# Nixie_Uhr.net
KiCad netlist of a schematic drawn in EAGLE
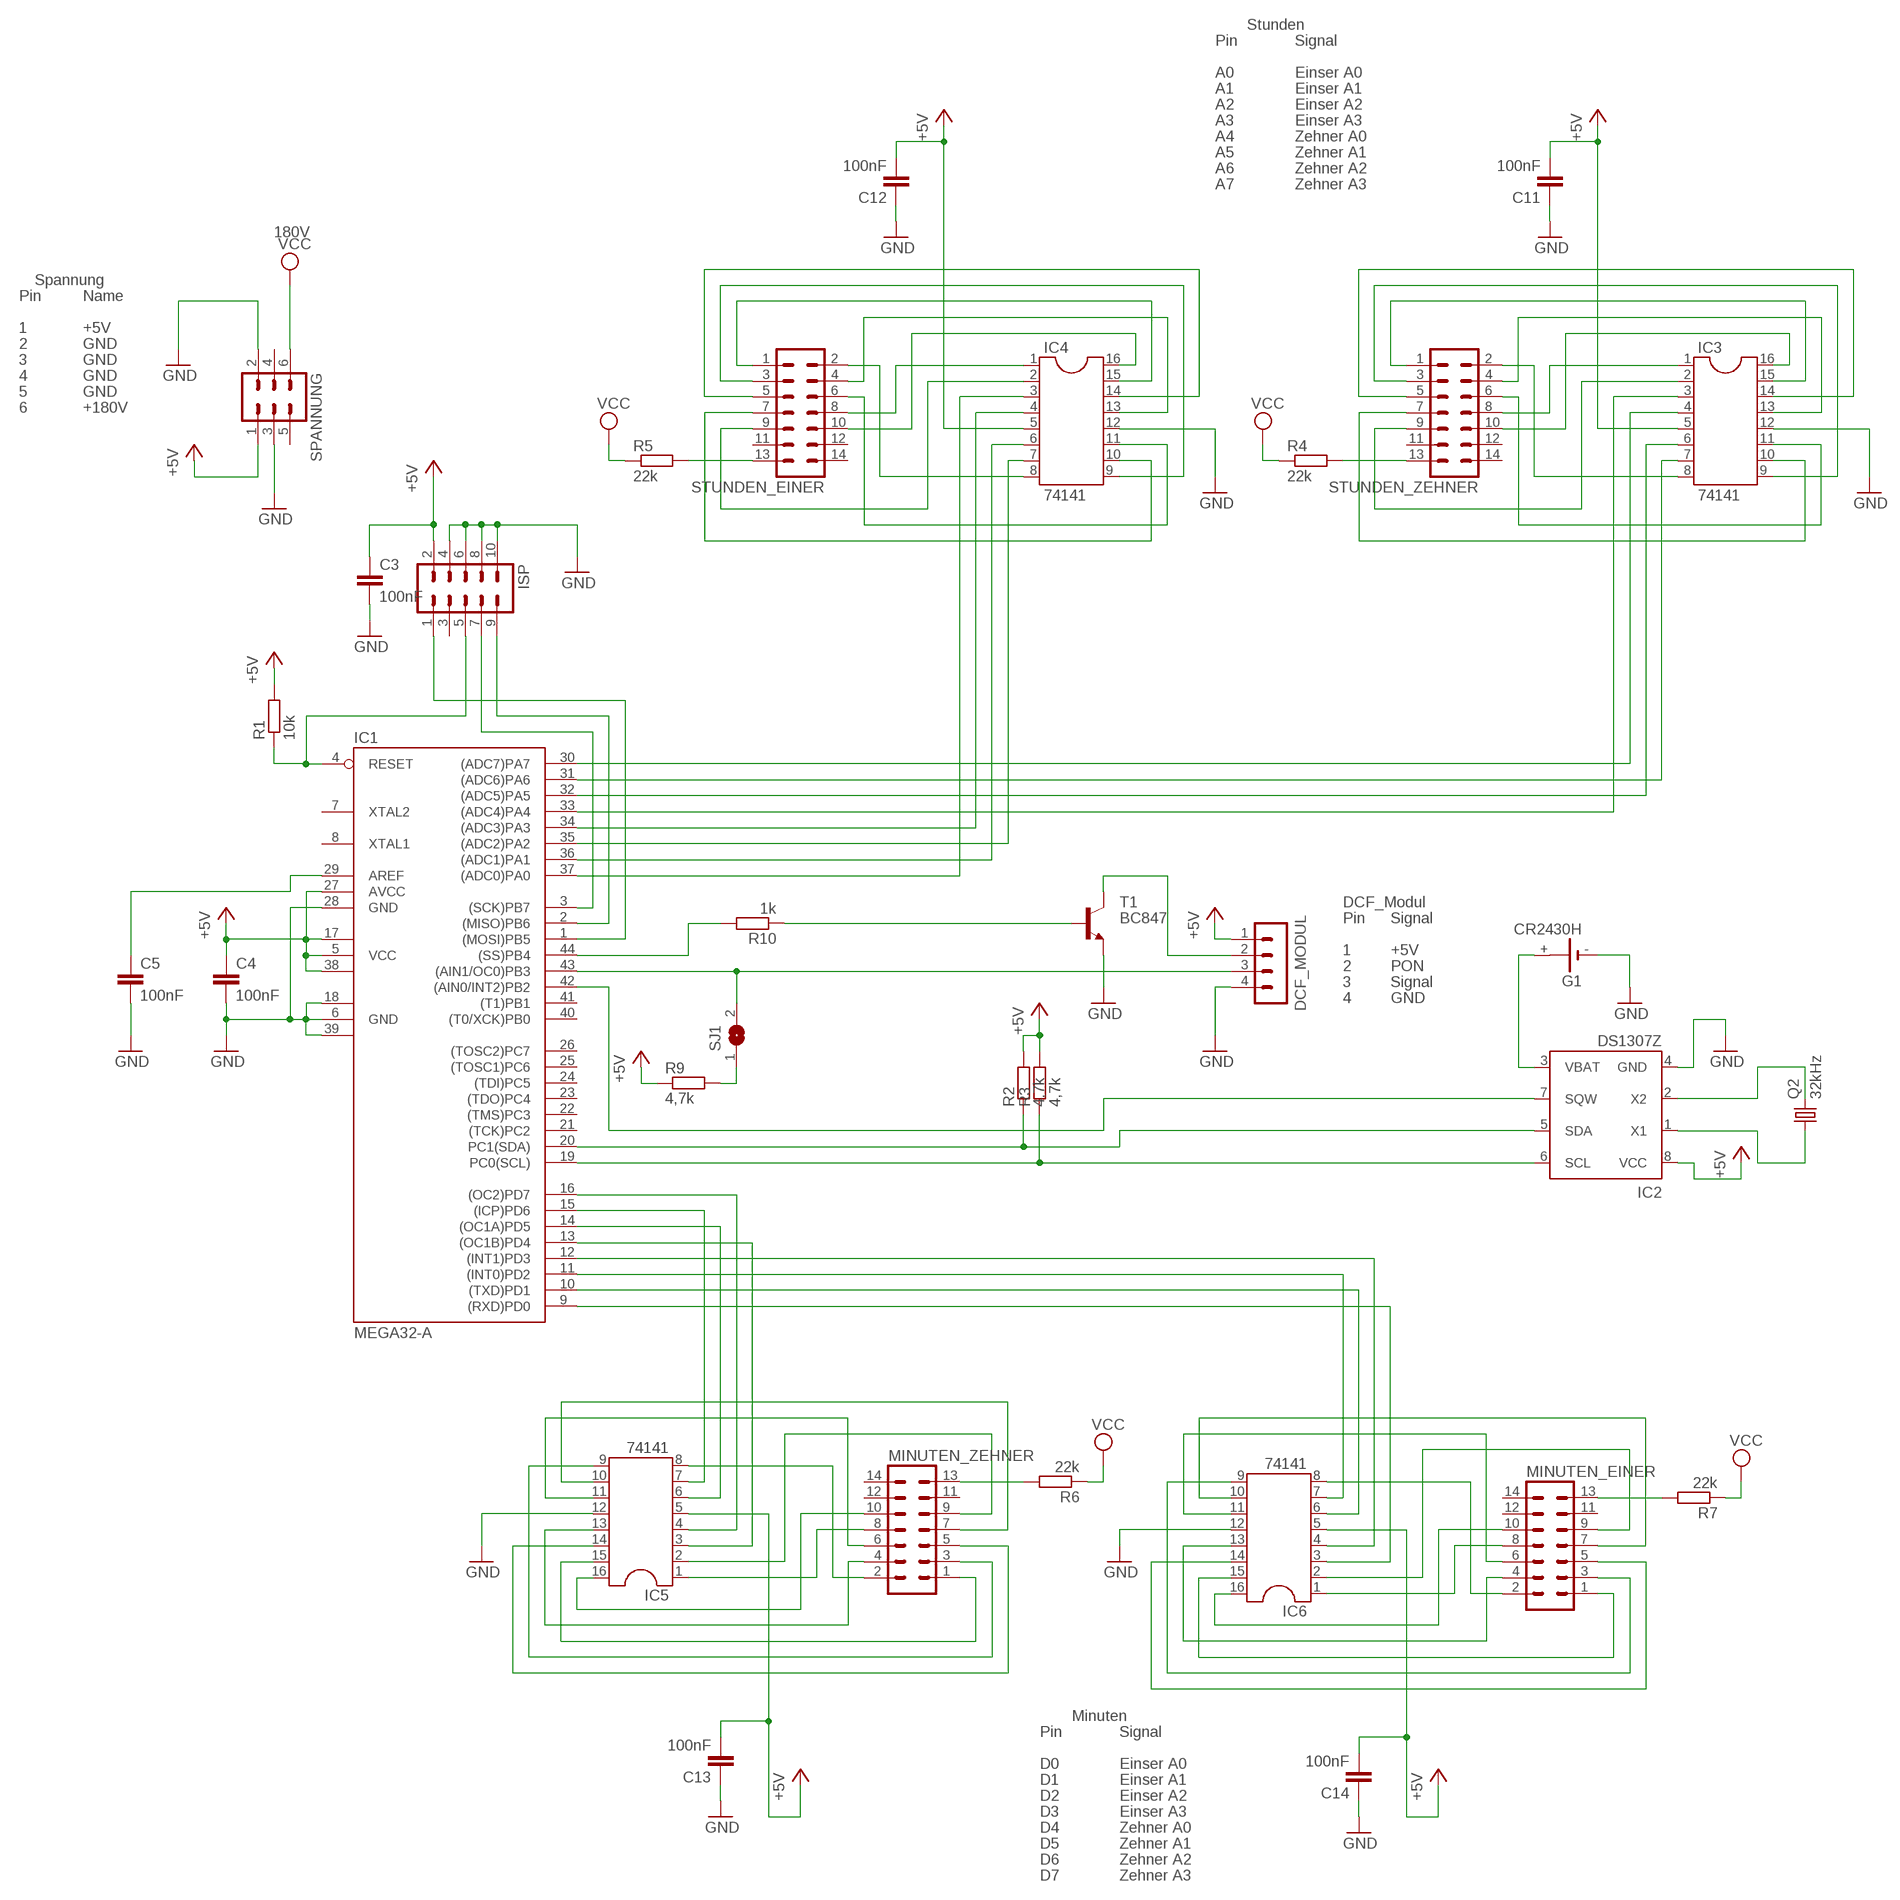
[diagram p0: schematic, sheet 1]

(export (version "E")
  (design (tool "Eeschema 10.0.6"))
  (components
    (comp (ref "C3")
      (value "100nF")
      (footprint "eagle-import:C0805")
      (libsource (lib "eagle-import") (part "C-EUC0805"))
    )
    (comp (ref "C4")
      (value "100nF")
      (footprint "eagle-import:C0805")
      (libsource (lib "eagle-import") (part "C-EUC0805"))
    )
    (comp (ref "C5")
      (value "100nF")
      (footprint "eagle-import:C0805")
      (libsource (lib "eagle-import") (part "C-EUC0805"))
    )
    (comp (ref "C11")
      (value "100nF")
      (footprint "eagle-import:C0805")
      (libsource (lib "eagle-import") (part "C-EUC0805"))
    )
    (comp (ref "C12")
      (value "100nF")
      (footprint "eagle-import:C0805")
      (libsource (lib "eagle-import") (part "C-EUC0805"))
    )
    (comp (ref "C13")
      (value "100nF")
      (footprint "eagle-import:C0805")
      (libsource (lib "eagle-import") (part "C-EUC0805"))
    )
    (comp (ref "C14")
      (value "100nF")
      (footprint "eagle-import:C0805")
      (libsource (lib "eagle-import") (part "C-EUC0805"))
    )
    (comp (ref "DCF_MODUL")
      (value "MA04-1")
      (footprint "eagle-import:MA04-1")
      (libsource (lib "eagle-import") (part "MA04-1"))
    )
    (comp (ref "G1")
      (value "CR2430H")
      (footprint "eagle-import:CR2430H")
      (libsource (lib "eagle-import") (part "CR2430H"))
    )
    (comp (ref "IC1")
      (value "MEGA32-A")
      (footprint "eagle-import:TQFP44")
      (fields (field (name "MPN") "ATMEGA32-16AU"))
      (libsource (lib "eagle-import") (part "MEGA32-A"))
    )
    (comp (ref "IC2")
      (value "DS1307Z")
      (footprint "eagle-import:SOIC8")
      (libsource (lib "eagle-import") (part "DS1307Z"))
    )
    (comp (ref "IC3")
      (value "74141")
      (footprint "eagle-import:DIL16")
      (libsource (lib "eagle-import") (part "DIL16"))
    )
    (comp (ref "IC4")
      (value "74141")
      (footprint "eagle-import:DIL16")
      (libsource (lib "eagle-import") (part "DIL16"))
    )
    (comp (ref "IC5")
      (value "74141")
      (footprint "eagle-import:DIL16")
      (libsource (lib "eagle-import") (part "DIL16"))
    )
    (comp (ref "IC6")
      (value "74141")
      (footprint "eagle-import:DIL16")
      (libsource (lib "eagle-import") (part "DIL16"))
    )
    (comp (ref "ISP")
      (value "ML10")
      (footprint "eagle-import:ML10")
      (libsource (lib "eagle-import") (part "ML10"))
    )
    (comp (ref "MINUTEN_EINER")
      (value "ML14")
      (footprint "eagle-import:ML14")
      (libsource (lib "eagle-import") (part "ML14"))
    )
    (comp (ref "MINUTEN_ZEHNER")
      (value "ML14")
      (footprint "eagle-import:ML14")
      (libsource (lib "eagle-import") (part "ML14"))
    )
    (comp (ref "Q2")
      (value "32kHz")
      (footprint "eagle-import:TC26V")
      (libsource (lib "eagle-import") (part "CRYSTALTC26V"))
    )
    (comp (ref "R1")
      (value "10k")
      (footprint "eagle-import:R0805")
      (libsource (lib "eagle-import") (part "R-EU_R0805"))
    )
    (comp (ref "R2")
      (value "4,7k")
      (footprint "eagle-import:R0805")
      (libsource (lib "eagle-import") (part "R-EU_R0805"))
    )
    (comp (ref "R3")
      (value "4,7k")
      (footprint "eagle-import:R0805")
      (libsource (lib "eagle-import") (part "R-EU_R0805"))
    )
    (comp (ref "R4")
      (value "22k")
      (footprint "eagle-import:0204_7")
      (libsource (lib "eagle-import") (part "R-EU_0204/7"))
    )
    (comp (ref "R5")
      (value "22k")
      (footprint "eagle-import:0204_7")
      (libsource (lib "eagle-import") (part "R-EU_0204/7"))
    )
    (comp (ref "R6")
      (value "22k")
      (footprint "eagle-import:0204_7")
      (libsource (lib "eagle-import") (part "R-EU_0204/7"))
    )
    (comp (ref "R7")
      (value "22k")
      (footprint "eagle-import:0204_7")
      (libsource (lib "eagle-import") (part "R-EU_0204/7"))
    )
    (comp (ref "R9")
      (value "4,7k")
      (footprint "eagle-import:R0805")
      (libsource (lib "eagle-import") (part "R-EU_R0805"))
    )
    (comp (ref "R10")
      (value "1k")
      (footprint "eagle-import:R0805")
      (libsource (lib "eagle-import") (part "R-EU_R0805"))
    )
    (comp (ref "SJ1") (value "SJ") (footprint "eagle-import:SJ") (libsource (lib "eagle-import") (part "SJ")))
    (comp (ref "SPANNUNG")
      (value "ML6")
      (footprint "eagle-import:ML6")
      (libsource (lib "eagle-import") (part "ML6"))
    )
    (comp (ref "STUNDEN_EINER")
      (value "ML14")
      (footprint "eagle-import:ML14")
      (libsource (lib "eagle-import") (part "ML14"))
    )
    (comp (ref "STUNDEN_ZEHNER")
      (value "ML14")
      (footprint "eagle-import:ML14")
      (libsource (lib "eagle-import") (part "ML14"))
    )
    (comp (ref "T1")
      (value "BC847")
      (footprint "eagle-import:SOT23")
      (libsource (lib "eagle-import") (part "BC847"))
    )
  )
  (nets
    (net (code "1") (name "+5V") (class "Default")
      (node (ref "C11") (pin "2") (pinfunction "2_2") (pintype "passive"))
      (node (ref "C12") (pin "2") (pinfunction "2_2") (pintype "passive"))
      (node (ref "C13") (pin "2") (pinfunction "2_2") (pintype "passive"))
      (node (ref "C14") (pin "2") (pinfunction "2_2") (pintype "passive"))
      (node (ref "C3") (pin "1") (pinfunction "1_1") (pintype "passive"))
      (node (ref "C4") (pin "1") (pinfunction "1_1") (pintype "passive"))
      (node (ref "DCF_MODUL") (pin "1") (pinfunction "1_1") (pintype "passive"))
      (node (ref "IC1") (pin "17") (pinfunction "VCC1_17") (pintype "power_in"))
      (node (ref "IC1") (pin "27") (pinfunction "AVCC_27") (pintype "power_in"))
      (node (ref "IC1") (pin "38") (pinfunction "VCC2_38") (pintype "power_in"))
      (node (ref "IC1") (pin "5") (pinfunction "VCC_5") (pintype "power_in"))
      (node (ref "IC2") (pin "8") (pinfunction "VCC_8") (pintype "power_in"))
      (node (ref "IC3") (pin "5") (pinfunction "5_5") (pintype "passive"))
      (node (ref "IC4") (pin "5") (pinfunction "5_5") (pintype "passive"))
      (node (ref "IC5") (pin "5") (pinfunction "5_5") (pintype "passive"))
      (node (ref "IC6") (pin "5") (pinfunction "5_5") (pintype "passive"))
      (node (ref "ISP") (pin "2") (pinfunction "2_2") (pintype "passive"))
      (node (ref "R1") (pin "2") (pinfunction "2_2") (pintype "passive"))
      (node (ref "R2") (pin "2") (pinfunction "2_2") (pintype "passive"))
      (node (ref "R3") (pin "2") (pinfunction "2_2") (pintype "passive"))
      (node (ref "R9") (pin "1") (pinfunction "1_1") (pintype "passive"))
      (node (ref "SPANNUNG") (pin "1") (pinfunction "1_1") (pintype "passive"))
    )
    (net (code "2") (name "GND") (class "Default")
      (node (ref "C11") (pin "1") (pinfunction "1_1") (pintype "passive"))
      (node (ref "C12") (pin "1") (pinfunction "1_1") (pintype "passive"))
      (node (ref "C13") (pin "1") (pinfunction "1_1") (pintype "passive"))
      (node (ref "C14") (pin "1") (pinfunction "1_1") (pintype "passive"))
      (node (ref "C3") (pin "2") (pinfunction "2_2") (pintype "passive"))
      (node (ref "C4") (pin "2") (pinfunction "2_2") (pintype "passive"))
      (node (ref "C5") (pin "2") (pinfunction "2_2") (pintype "passive"))
      (node (ref "DCF_MODUL") (pin "4") (pinfunction "4_4") (pintype "passive"))
      (node (ref "G1") (pin "-") (pinfunction "-_-") (pintype "passive"))
      (node (ref "IC1") (pin "18") (pinfunction "GND1_18") (pintype "power_in"))
      (node (ref "IC1") (pin "28") (pinfunction "GND_28") (pintype "power_in"))
      (node (ref "IC1") (pin "39") (pinfunction "GND2_39") (pintype "power_in"))
      (node (ref "IC1") (pin "6") (pinfunction "GND_6") (pintype "power_in"))
      (node (ref "IC2") (pin "4") (pinfunction "GND_4") (pintype "power_in"))
      (node (ref "IC3") (pin "12") (pinfunction "12_12") (pintype "passive"))
      (node (ref "IC4") (pin "12") (pinfunction "12_12") (pintype "passive"))
      (node (ref "IC5") (pin "12") (pinfunction "12_12") (pintype "passive"))
      (node (ref "IC6") (pin "12") (pinfunction "12_12") (pintype "passive"))
      (node (ref "ISP") (pin "10") (pinfunction "10_10") (pintype "passive"))
      (node (ref "ISP") (pin "4") (pinfunction "4_4") (pintype "passive"))
      (node (ref "ISP") (pin "6") (pinfunction "6_6") (pintype "passive"))
      (node (ref "ISP") (pin "8") (pinfunction "8_8") (pintype "passive"))
      (node (ref "SPANNUNG") (pin "2") (pinfunction "2_2") (pintype "passive"))
      (node (ref "SPANNUNG") (pin "3") (pinfunction "3_3") (pintype "passive"))
      (node (ref "T1") (pin "2") (pinfunction "E_2") (pintype "passive"))
    )
    (net (code "3") (name "Net-(IC1-(ADC0)PA0)") (class "Default")
      (node (ref "IC1") (pin "37") (pinfunction "(ADC0)PA0_37") (pintype "bidirectional"))
      (node (ref "IC4") (pin "3") (pinfunction "3_3") (pintype "passive"))
    )
    (net (code "4") (name "Net-(IC1-(ADC1)PA1)") (class "Default")
      (node (ref "IC1") (pin "36") (pinfunction "(ADC1)PA1_36") (pintype "bidirectional"))
      (node (ref "IC4") (pin "6") (pinfunction "6_6") (pintype "passive"))
    )
    (net (code "5") (name "Net-(IC1-(ADC2)PA2)") (class "Default")
      (node (ref "IC1") (pin "35") (pinfunction "(ADC2)PA2_35") (pintype "bidirectional"))
      (node (ref "IC4") (pin "7") (pinfunction "7_7") (pintype "passive"))
    )
    (net (code "6") (name "Net-(IC1-(ADC3)PA3)") (class "Default")
      (node (ref "IC1") (pin "34") (pinfunction "(ADC3)PA3_34") (pintype "bidirectional"))
      (node (ref "IC4") (pin "4") (pinfunction "4_4") (pintype "passive"))
    )
    (net (code "7") (name "Net-(IC1-(ADC4)PA4)") (class "Default")
      (node (ref "IC1") (pin "33") (pinfunction "(ADC4)PA4_33") (pintype "bidirectional"))
      (node (ref "IC3") (pin "3") (pinfunction "3_3") (pintype "passive"))
    )
    (net (code "8") (name "Net-(IC1-(ADC5)PA5)") (class "Default")
      (node (ref "IC1") (pin "32") (pinfunction "(ADC5)PA5_32") (pintype "bidirectional"))
      (node (ref "IC3") (pin "6") (pinfunction "6_6") (pintype "passive"))
    )
    (net (code "9") (name "Net-(IC1-(ADC6)PA6)") (class "Default")
      (node (ref "IC1") (pin "31") (pinfunction "(ADC6)PA6_31") (pintype "bidirectional"))
      (node (ref "IC3") (pin "7") (pinfunction "7_7") (pintype "passive"))
    )
    (net (code "10") (name "Net-(IC1-(ADC7)PA7)") (class "Default")
      (node (ref "IC1") (pin "30") (pinfunction "(ADC7)PA7_30") (pintype "bidirectional"))
      (node (ref "IC3") (pin "4") (pinfunction "4_4") (pintype "passive"))
    )
    (net (code "11") (name "Net-(IC1-(AIN0{slash}INT2)PB2)") (class "Default")
      (node (ref "IC1") (pin "42") (pinfunction "(AIN0/INT2)PB2_42") (pintype "bidirectional"))
      (node (ref "IC2") (pin "7") (pinfunction "SQW_7") (pintype "open_collector"))
    )
    (net (code "12") (name "Net-(IC1-(AIN1{slash}OC0)PB3)") (class "Default")
      (node (ref "DCF_MODUL") (pin "3") (pinfunction "3_3") (pintype "passive"))
      (node (ref "IC1") (pin "43") (pinfunction "(AIN1/OC0)PB3_43") (pintype "bidirectional"))
      (node (ref "SJ1") (pin "2") (pinfunction "2_2") (pintype "passive"))
    )
    (net (code "13") (name "Net-(IC1-(ICP)PD6)") (class "Default")
      (node (ref "IC1") (pin "15") (pinfunction "(ICP)PD6_15") (pintype "bidirectional"))
      (node (ref "IC5") (pin "7") (pinfunction "7_7") (pintype "passive"))
    )
    (net (code "14") (name "Net-(IC1-(INT0)PD2)") (class "Default")
      (node (ref "IC1") (pin "11") (pinfunction "(INT0)PD2_11") (pintype "bidirectional"))
      (node (ref "IC6") (pin "7") (pinfunction "7_7") (pintype "passive"))
    )
    (net (code "15") (name "Net-(IC1-(INT1)PD3)") (class "Default")
      (node (ref "IC1") (pin "12") (pinfunction "(INT1)PD3_12") (pintype "bidirectional"))
      (node (ref "IC6") (pin "4") (pinfunction "4_4") (pintype "passive"))
    )
    (net (code "16") (name "Net-(IC1-(MISO)PB6)") (class "Default")
      (node (ref "IC1") (pin "2") (pinfunction "(MISO)PB6_2") (pintype "bidirectional"))
      (node (ref "ISP") (pin "9") (pinfunction "9_9") (pintype "passive"))
    )
    (net (code "17") (name "Net-(IC1-(MOSI)PB5)") (class "Default")
      (node (ref "IC1") (pin "1") (pinfunction "(MOSI)PB5_1") (pintype "bidirectional"))
      (node (ref "ISP") (pin "1") (pinfunction "1_1") (pintype "passive"))
    )
    (net (code "18") (name "Net-(IC1-(OC1A)PD5)") (class "Default")
      (node (ref "IC1") (pin "14") (pinfunction "(OC1A)PD5_14") (pintype "bidirectional"))
      (node (ref "IC5") (pin "6") (pinfunction "6_6") (pintype "passive"))
    )
    (net (code "19") (name "Net-(IC1-(OC1B)PD4)") (class "Default")
      (node (ref "IC1") (pin "13") (pinfunction "(OC1B)PD4_13") (pintype "bidirectional"))
      (node (ref "IC5") (pin "3") (pinfunction "3_3") (pintype "passive"))
    )
    (net (code "20") (name "Net-(IC1-(OC2)PD7)") (class "Default")
      (node (ref "IC1") (pin "16") (pinfunction "(OC2)PD7_16") (pintype "bidirectional"))
      (node (ref "IC5") (pin "4") (pinfunction "4_4") (pintype "passive"))
    )
    (net (code "21") (name "Net-(IC1-(RXD)PD0)") (class "Default")
      (node (ref "IC1") (pin "9") (pinfunction "(RXD)PD0_9") (pintype "bidirectional"))
      (node (ref "IC6") (pin "3") (pinfunction "3_3") (pintype "passive"))
    )
    (net (code "22") (name "Net-(IC1-(SCK)PB7)") (class "Default")
      (node (ref "IC1") (pin "3") (pinfunction "(SCK)PB7_3") (pintype "bidirectional"))
      (node (ref "ISP") (pin "7") (pinfunction "7_7") (pintype "passive"))
    )
    (net (code "23") (name "Net-(IC1-(SS)PB4)") (class "Default")
      (node (ref "IC1") (pin "44") (pinfunction "(SS)PB4_44") (pintype "bidirectional"))
      (node (ref "R10") (pin "2") (pinfunction "2_2") (pintype "passive"))
    )
    (net (code "24") (name "Net-(IC1-(TXD)PD1)") (class "Default")
      (node (ref "IC1") (pin "10") (pinfunction "(TXD)PD1_10") (pintype "bidirectional"))
      (node (ref "IC6") (pin "6") (pinfunction "6_6") (pintype "passive"))
    )
    (net (code "25") (name "Net-(IC1-AREF)") (class "Default")
      (node (ref "C5") (pin "1") (pinfunction "1_1") (pintype "passive"))
      (node (ref "IC1") (pin "29") (pinfunction "AREF_29") (pintype "passive"))
    )
    (net (code "26") (name "Net-(IC1-PC0(SCL))") (class "Default")
      (node (ref "IC1") (pin "19") (pinfunction "PC0(SCL)_19") (pintype "bidirectional"))
      (node (ref "IC2") (pin "6") (pinfunction "SCL_6") (pintype "input"))
      (node (ref "R3") (pin "1") (pinfunction "1_1") (pintype "passive"))
    )
    (net (code "27") (name "Net-(IC1-PC1(SDA))") (class "Default")
      (node (ref "IC1") (pin "20") (pinfunction "PC1(SDA)_20") (pintype "bidirectional"))
      (node (ref "IC2") (pin "5") (pinfunction "SDA_5") (pintype "bidirectional"))
      (node (ref "R2") (pin "1") (pinfunction "1_1") (pintype "passive"))
    )
    (net (code "28") (name "Net-(IC1-RESET)") (class "Default")
      (node (ref "IC1") (pin "4") (pinfunction "RESET_4") (pintype "input"))
      (node (ref "ISP") (pin "5") (pinfunction "5_5") (pintype "passive"))
      (node (ref "R1") (pin "1") (pinfunction "1_1") (pintype "passive"))
    )
    (net (code "29") (name "Net-(IC2-VBAT)") (class "Default")
      (node (ref "G1") (pin "+") (pinfunction "+_+") (pintype "passive"))
      (node (ref "IC2") (pin "3") (pinfunction "VBAT_3") (pintype "passive"))
    )
    (net (code "30") (name "Net-(IC2-X1)") (class "Default")
      (node (ref "IC2") (pin "1") (pinfunction "X1_1") (pintype "input"))
      (node (ref "Q2") (pin "1") (pinfunction "1_1") (pintype "passive"))
    )
    (net (code "31") (name "Net-(IC2-X2)") (class "Default")
      (node (ref "IC2") (pin "2") (pinfunction "X2_2") (pintype "output"))
      (node (ref "Q2") (pin "2") (pinfunction "2_2") (pintype "passive"))
    )
    (net (code "32") (name "Net-(IC3-Pad1)") (class "Default")
      (node (ref "IC3") (pin "1") (pinfunction "1_1") (pintype "passive"))
      (node (ref "STUNDEN_ZEHNER") (pin "8") (pinfunction "8_8") (pintype "passive"))
    )
    (net (code "33") (name "Net-(IC3-Pad2)") (class "Default")
      (node (ref "IC3") (pin "2") (pinfunction "2_2") (pintype "passive"))
      (node (ref "STUNDEN_ZEHNER") (pin "9") (pinfunction "9_9") (pintype "passive"))
    )
    (net (code "34") (name "Net-(IC3-Pad8)") (class "Default")
      (node (ref "IC3") (pin "8") (pinfunction "8_8") (pintype "passive"))
      (node (ref "STUNDEN_ZEHNER") (pin "2") (pinfunction "2_2") (pintype "passive"))
    )
    (net (code "35") (name "Net-(IC3-Pad9)") (class "Default")
      (node (ref "IC3") (pin "9") (pinfunction "9_9") (pintype "passive"))
      (node (ref "STUNDEN_ZEHNER") (pin "3") (pinfunction "3_3") (pintype "passive"))
    )
    (net (code "36") (name "Net-(IC3-Pad10)") (class "Default")
      (node (ref "IC3") (pin "10") (pinfunction "10_10") (pintype "passive"))
      (node (ref "STUNDEN_ZEHNER") (pin "7") (pinfunction "7_7") (pintype "passive"))
    )
    (net (code "37") (name "Net-(IC3-Pad11)") (class "Default")
      (node (ref "IC3") (pin "11") (pinfunction "11_11") (pintype "passive"))
      (node (ref "STUNDEN_ZEHNER") (pin "6") (pinfunction "6_6") (pintype "passive"))
    )
    (net (code "38") (name "Net-(IC3-Pad13)") (class "Default")
      (node (ref "IC3") (pin "13") (pinfunction "13_13") (pintype "passive"))
      (node (ref "STUNDEN_ZEHNER") (pin "4") (pinfunction "4_4") (pintype "passive"))
    )
    (net (code "39") (name "Net-(IC3-Pad14)") (class "Default")
      (node (ref "IC3") (pin "14") (pinfunction "14_14") (pintype "passive"))
      (node (ref "STUNDEN_ZEHNER") (pin "5") (pinfunction "5_5") (pintype "passive"))
    )
    (net (code "40") (name "Net-(IC3-Pad15)") (class "Default")
      (node (ref "IC3") (pin "15") (pinfunction "15_15") (pintype "passive"))
      (node (ref "STUNDEN_ZEHNER") (pin "1") (pinfunction "1_1") (pintype "passive"))
    )
    (net (code "41") (name "Net-(IC3-Pad16)") (class "Default")
      (node (ref "IC3") (pin "16") (pinfunction "16_16") (pintype "passive"))
      (node (ref "STUNDEN_ZEHNER") (pin "10") (pinfunction "10_10") (pintype "passive"))
    )
    (net (code "42") (name "Net-(IC4-Pad1)") (class "Default")
      (node (ref "IC4") (pin "1") (pinfunction "1_1") (pintype "passive"))
      (node (ref "STUNDEN_EINER") (pin "8") (pinfunction "8_8") (pintype "passive"))
    )
    (net (code "43") (name "Net-(IC4-Pad2)") (class "Default")
      (node (ref "IC4") (pin "2") (pinfunction "2_2") (pintype "passive"))
      (node (ref "STUNDEN_EINER") (pin "9") (pinfunction "9_9") (pintype "passive"))
    )
    (net (code "44") (name "Net-(IC4-Pad8)") (class "Default")
      (node (ref "IC4") (pin "8") (pinfunction "8_8") (pintype "passive"))
      (node (ref "STUNDEN_EINER") (pin "2") (pinfunction "2_2") (pintype "passive"))
    )
    (net (code "45") (name "Net-(IC4-Pad9)") (class "Default")
      (node (ref "IC4") (pin "9") (pinfunction "9_9") (pintype "passive"))
      (node (ref "STUNDEN_EINER") (pin "3") (pinfunction "3_3") (pintype "passive"))
    )
    (net (code "46") (name "Net-(IC4-Pad10)") (class "Default")
      (node (ref "IC4") (pin "10") (pinfunction "10_10") (pintype "passive"))
      (node (ref "STUNDEN_EINER") (pin "7") (pinfunction "7_7") (pintype "passive"))
    )
    (net (code "47") (name "Net-(IC4-Pad11)") (class "Default")
      (node (ref "IC4") (pin "11") (pinfunction "11_11") (pintype "passive"))
      (node (ref "STUNDEN_EINER") (pin "6") (pinfunction "6_6") (pintype "passive"))
    )
    (net (code "48") (name "Net-(IC4-Pad13)") (class "Default")
      (node (ref "IC4") (pin "13") (pinfunction "13_13") (pintype "passive"))
      (node (ref "STUNDEN_EINER") (pin "4") (pinfunction "4_4") (pintype "passive"))
    )
    (net (code "49") (name "Net-(IC4-Pad14)") (class "Default")
      (node (ref "IC4") (pin "14") (pinfunction "14_14") (pintype "passive"))
      (node (ref "STUNDEN_EINER") (pin "5") (pinfunction "5_5") (pintype "passive"))
    )
    (net (code "50") (name "Net-(IC4-Pad15)") (class "Default")
      (node (ref "IC4") (pin "15") (pinfunction "15_15") (pintype "passive"))
      (node (ref "STUNDEN_EINER") (pin "1") (pinfunction "1_1") (pintype "passive"))
    )
    (net (code "51") (name "Net-(IC4-Pad16)") (class "Default")
      (node (ref "IC4") (pin "16") (pinfunction "16_16") (pintype "passive"))
      (node (ref "STUNDEN_EINER") (pin "10") (pinfunction "10_10") (pintype "passive"))
    )
    (net (code "52") (name "Net-(IC5-Pad1)") (class "Default")
      (node (ref "IC5") (pin "1") (pinfunction "1_1") (pintype "passive"))
      (node (ref "MINUTEN_ZEHNER") (pin "8") (pinfunction "8_8") (pintype "passive"))
    )
    (net (code "53") (name "Net-(IC5-Pad2)") (class "Default")
      (node (ref "IC5") (pin "2") (pinfunction "2_2") (pintype "passive"))
      (node (ref "MINUTEN_ZEHNER") (pin "9") (pinfunction "9_9") (pintype "passive"))
    )
    (net (code "54") (name "Net-(IC5-Pad8)") (class "Default")
      (node (ref "IC5") (pin "8") (pinfunction "8_8") (pintype "passive"))
      (node (ref "MINUTEN_ZEHNER") (pin "2") (pinfunction "2_2") (pintype "passive"))
    )
    (net (code "55") (name "Net-(IC5-Pad9)") (class "Default")
      (node (ref "IC5") (pin "9") (pinfunction "9_9") (pintype "passive"))
      (node (ref "MINUTEN_ZEHNER") (pin "3") (pinfunction "3_3") (pintype "passive"))
    )
    (net (code "56") (name "Net-(IC5-Pad10)") (class "Default")
      (node (ref "IC5") (pin "10") (pinfunction "10_10") (pintype "passive"))
      (node (ref "MINUTEN_ZEHNER") (pin "7") (pinfunction "7_7") (pintype "passive"))
    )
    (net (code "57") (name "Net-(IC5-Pad11)") (class "Default")
      (node (ref "IC5") (pin "11") (pinfunction "11_11") (pintype "passive"))
      (node (ref "MINUTEN_ZEHNER") (pin "6") (pinfunction "6_6") (pintype "passive"))
    )
    (net (code "58") (name "Net-(IC5-Pad13)") (class "Default")
      (node (ref "IC5") (pin "13") (pinfunction "13_13") (pintype "passive"))
      (node (ref "MINUTEN_ZEHNER") (pin "4") (pinfunction "4_4") (pintype "passive"))
    )
    (net (code "59") (name "Net-(IC5-Pad14)") (class "Default")
      (node (ref "IC5") (pin "14") (pinfunction "14_14") (pintype "passive"))
      (node (ref "MINUTEN_ZEHNER") (pin "5") (pinfunction "5_5") (pintype "passive"))
    )
    (net (code "60") (name "Net-(IC5-Pad15)") (class "Default")
      (node (ref "IC5") (pin "15") (pinfunction "15_15") (pintype "passive"))
      (node (ref "MINUTEN_ZEHNER") (pin "1") (pinfunction "1_1") (pintype "passive"))
    )
    (net (code "61") (name "Net-(IC5-Pad16)") (class "Default")
      (node (ref "IC5") (pin "16") (pinfunction "16_16") (pintype "passive"))
      (node (ref "MINUTEN_ZEHNER") (pin "10") (pinfunction "10_10") (pintype "passive"))
    )
    (net (code "62") (name "Net-(IC6-Pad1)") (class "Default")
      (node (ref "IC6") (pin "1") (pinfunction "1_1") (pintype "passive"))
      (node (ref "MINUTEN_EINER") (pin "8") (pinfunction "8_8") (pintype "passive"))
    )
    (net (code "63") (name "Net-(IC6-Pad2)") (class "Default")
      (node (ref "IC6") (pin "2") (pinfunction "2_2") (pintype "passive"))
      (node (ref "MINUTEN_EINER") (pin "9") (pinfunction "9_9") (pintype "passive"))
    )
    (net (code "64") (name "Net-(IC6-Pad8)") (class "Default")
      (node (ref "IC6") (pin "8") (pinfunction "8_8") (pintype "passive"))
      (node (ref "MINUTEN_EINER") (pin "2") (pinfunction "2_2") (pintype "passive"))
    )
    (net (code "65") (name "Net-(IC6-Pad9)") (class "Default")
      (node (ref "IC6") (pin "9") (pinfunction "9_9") (pintype "passive"))
      (node (ref "MINUTEN_EINER") (pin "3") (pinfunction "3_3") (pintype "passive"))
    )
    (net (code "66") (name "Net-(IC6-Pad10)") (class "Default")
      (node (ref "IC6") (pin "10") (pinfunction "10_10") (pintype "passive"))
      (node (ref "MINUTEN_EINER") (pin "7") (pinfunction "7_7") (pintype "passive"))
    )
    (net (code "67") (name "Net-(IC6-Pad11)") (class "Default")
      (node (ref "IC6") (pin "11") (pinfunction "11_11") (pintype "passive"))
      (node (ref "MINUTEN_EINER") (pin "6") (pinfunction "6_6") (pintype "passive"))
    )
    (net (code "68") (name "Net-(IC6-Pad13)") (class "Default")
      (node (ref "IC6") (pin "13") (pinfunction "13_13") (pintype "passive"))
      (node (ref "MINUTEN_EINER") (pin "4") (pinfunction "4_4") (pintype "passive"))
    )
    (net (code "69") (name "Net-(IC6-Pad14)") (class "Default")
      (node (ref "IC6") (pin "14") (pinfunction "14_14") (pintype "passive"))
      (node (ref "MINUTEN_EINER") (pin "5") (pinfunction "5_5") (pintype "passive"))
    )
    (net (code "70") (name "Net-(IC6-Pad15)") (class "Default")
      (node (ref "IC6") (pin "15") (pinfunction "15_15") (pintype "passive"))
      (node (ref "MINUTEN_EINER") (pin "1") (pinfunction "1_1") (pintype "passive"))
    )
    (net (code "71") (name "Net-(IC6-Pad16)") (class "Default")
      (node (ref "IC6") (pin "16") (pinfunction "16_16") (pintype "passive"))
      (node (ref "MINUTEN_EINER") (pin "10") (pinfunction "10_10") (pintype "passive"))
    )
    (net (code "72") (name "Net-(MINUTEN_EINER-Pad13)") (class "Default")
      (node (ref "MINUTEN_EINER") (pin "13") (pinfunction "13_13") (pintype "passive"))
      (node (ref "R7") (pin "2") (pinfunction "2_2") (pintype "passive"))
    )
    (net (code "73") (name "Net-(MINUTEN_ZEHNER-Pad13)") (class "Default")
      (node (ref "MINUTEN_ZEHNER") (pin "13") (pinfunction "13_13") (pintype "passive"))
      (node (ref "R6") (pin "2") (pinfunction "2_2") (pintype "passive"))
    )
    (net (code "74") (name "Net-(R4-Pad2)") (class "Default")
      (node (ref "R4") (pin "2") (pinfunction "2_2") (pintype "passive"))
      (node (ref "STUNDEN_ZEHNER") (pin "13") (pinfunction "13_13") (pintype "passive"))
    )
    (net (code "75") (name "Net-(R5-Pad2)") (class "Default")
      (node (ref "R5") (pin "2") (pinfunction "2_2") (pintype "passive"))
      (node (ref "STUNDEN_EINER") (pin "13") (pinfunction "13_13") (pintype "passive"))
    )
    (net (code "76") (name "Net-(R9-Pad2)") (class "Default")
      (node (ref "R9") (pin "2") (pinfunction "2_2") (pintype "passive"))
      (node (ref "SJ1") (pin "1") (pinfunction "1_1") (pintype "passive"))
    )
    (net (code "77") (name "Net-(T1-B)") (class "Default")
      (node (ref "R10") (pin "1") (pinfunction "1_1") (pintype "passive"))
      (node (ref "T1") (pin "1") (pinfunction "B_1") (pintype "passive"))
    )
    (net (code "78") (name "Net-(T1-C)") (class "Default")
      (node (ref "DCF_MODUL") (pin "2") (pinfunction "2_2") (pintype "passive"))
      (node (ref "T1") (pin "3") (pinfunction "C_3") (pintype "passive"))
    )
    (net (code "79") (name "VCC") (class "Default")
      (node (ref "R4") (pin "1") (pinfunction "1_1") (pintype "passive"))
      (node (ref "R5") (pin "1") (pinfunction "1_1") (pintype "passive"))
      (node (ref "R6") (pin "1") (pinfunction "1_1") (pintype "passive"))
      (node (ref "R7") (pin "1") (pinfunction "1_1") (pintype "passive"))
      (node (ref "SPANNUNG") (pin "6") (pinfunction "6_6") (pintype "passive"))
    )
    (net (code "80") (name "unconnected-(G1-+-Pad+@1)") (class "Default")
      (node (ref "G1") (pin "+@1") (pinfunction "+_+@1") (pintype "passive"))
    )
    (net (code "81") (name "unconnected-(IC1-(T0{slash}XCK)PB0-Pad40)") (class "Default")
      (node (ref "IC1") (pin "40") (pinfunction "(T0/XCK)PB0_40") (pintype "bidirectional"))
    )
    (net (code "82") (name "unconnected-(IC1-(T1)PB1-Pad41)") (class "Default")
      (node (ref "IC1") (pin "41") (pinfunction "(T1)PB1_41") (pintype "bidirectional"))
    )
    (net (code "83") (name "unconnected-(IC1-(TCK)PC2-Pad21)") (class "Default")
      (node (ref "IC1") (pin "21") (pinfunction "(TCK)PC2_21") (pintype "bidirectional"))
    )
    (net (code "84") (name "unconnected-(IC1-(TDI)PC5-Pad24)") (class "Default")
      (node (ref "IC1") (pin "24") (pinfunction "(TDI)PC5_24") (pintype "bidirectional"))
    )
    (net (code "85") (name "unconnected-(IC1-(TDO)PC4-Pad23)") (class "Default")
      (node (ref "IC1") (pin "23") (pinfunction "(TDO)PC4_23") (pintype "bidirectional"))
    )
    (net (code "86") (name "unconnected-(IC1-(TMS)PC3-Pad22)") (class "Default")
      (node (ref "IC1") (pin "22") (pinfunction "(TMS)PC3_22") (pintype "bidirectional"))
    )
    (net (code "87") (name "unconnected-(IC1-(TOSC1)PC6-Pad25)") (class "Default")
      (node (ref "IC1") (pin "25") (pinfunction "(TOSC1)PC6_25") (pintype "bidirectional"))
    )
    (net (code "88") (name "unconnected-(IC1-(TOSC2)PC7-Pad26)") (class "Default")
      (node (ref "IC1") (pin "26") (pinfunction "(TOSC2)PC7_26") (pintype "bidirectional"))
    )
    (net (code "89") (name "unconnected-(IC1-XTAL1-Pad8)") (class "Default")
      (node (ref "IC1") (pin "8") (pinfunction "XTAL1_8") (pintype "bidirectional"))
    )
    (net (code "90") (name "unconnected-(IC1-XTAL2-Pad7)") (class "Default")
      (node (ref "IC1") (pin "7") (pinfunction "XTAL2_7") (pintype "bidirectional"))
    )
    (net (code "91") (name "unconnected-(ISP-Pad3)") (class "Default")
      (node (ref "ISP") (pin "3") (pinfunction "3_3") (pintype "passive"))
    )
    (net (code "92") (name "unconnected-(MINUTEN_EINER-Pad11)") (class "Default")
      (node (ref "MINUTEN_EINER") (pin "11") (pinfunction "11_11") (pintype "passive"))
    )
    (net (code "93") (name "unconnected-(MINUTEN_EINER-Pad12)") (class "Default")
      (node (ref "MINUTEN_EINER") (pin "12") (pinfunction "12_12") (pintype "passive"))
    )
    (net (code "94") (name "unconnected-(MINUTEN_EINER-Pad14)") (class "Default")
      (node (ref "MINUTEN_EINER") (pin "14") (pinfunction "14_14") (pintype "passive"))
    )
    (net (code "95") (name "unconnected-(MINUTEN_ZEHNER-Pad11)") (class "Default")
      (node (ref "MINUTEN_ZEHNER") (pin "11") (pinfunction "11_11") (pintype "passive"))
    )
    (net (code "96") (name "unconnected-(MINUTEN_ZEHNER-Pad12)") (class "Default")
      (node (ref "MINUTEN_ZEHNER") (pin "12") (pinfunction "12_12") (pintype "passive"))
    )
    (net (code "97") (name "unconnected-(MINUTEN_ZEHNER-Pad14)") (class "Default")
      (node (ref "MINUTEN_ZEHNER") (pin "14") (pinfunction "14_14") (pintype "passive"))
    )
    (net (code "98") (name "unconnected-(SPANNUNG-Pad4)") (class "Default")
      (node (ref "SPANNUNG") (pin "4") (pinfunction "4_4") (pintype "passive"))
    )
    (net (code "99") (name "unconnected-(SPANNUNG-Pad5)") (class "Default")
      (node (ref "SPANNUNG") (pin "5") (pinfunction "5_5") (pintype "passive"))
    )
    (net (code "100") (name "unconnected-(STUNDEN_EINER-Pad11)") (class "Default")
      (node (ref "STUNDEN_EINER") (pin "11") (pinfunction "11_11") (pintype "passive"))
    )
    (net (code "101") (name "unconnected-(STUNDEN_EINER-Pad12)") (class "Default")
      (node (ref "STUNDEN_EINER") (pin "12") (pinfunction "12_12") (pintype "passive"))
    )
    (net (code "102") (name "unconnected-(STUNDEN_EINER-Pad14)") (class "Default")
      (node (ref "STUNDEN_EINER") (pin "14") (pinfunction "14_14") (pintype "passive"))
    )
    (net (code "103") (name "unconnected-(STUNDEN_ZEHNER-Pad11)") (class "Default")
      (node (ref "STUNDEN_ZEHNER") (pin "11") (pinfunction "11_11") (pintype "passive"))
    )
    (net (code "104") (name "unconnected-(STUNDEN_ZEHNER-Pad12)") (class "Default")
      (node (ref "STUNDEN_ZEHNER") (pin "12") (pinfunction "12_12") (pintype "passive"))
    )
    (net (code "105") (name "unconnected-(STUNDEN_ZEHNER-Pad14)") (class "Default")
      (node (ref "STUNDEN_ZEHNER") (pin "14") (pinfunction "14_14") (pintype "passive"))
    )
  )
)
